# RC_car.net
KiCad netlist of a schematic drawn in EAGLE
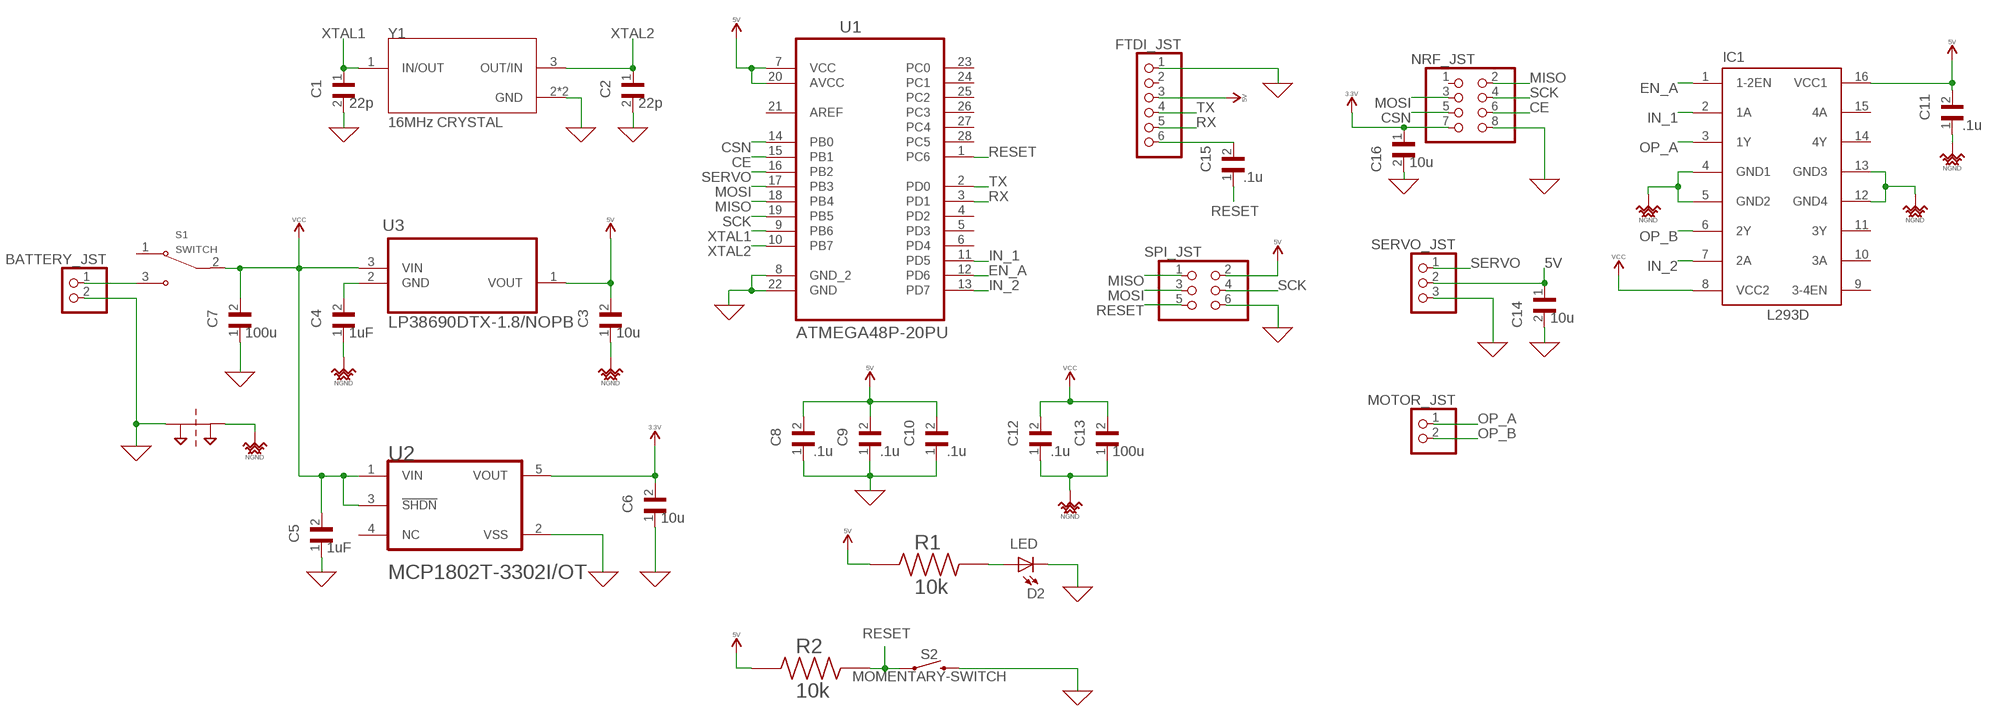
[diagram p0: schematic, sheet 1]

(export (version "E")
  (design (tool "Eeschema 10.0.6"))
  (components
    (comp (ref "BATTERY_JST")
      (value "PINHD-1X2")
      (footprint "eagle-import:1X02")
      (libsource (lib "eagle-import") (part "PINHD-1X2"))
    )
    (comp (ref "C1")
      (value "22p")
      (footprint "eagle-import:CAPC2012X140N")
      (fields
        (field (name "DIGI-KEY_PART_NUMBER") "399-C0805C220J5GAC7800CT-ND")
        (field (name "MF") "KEMET")
        (field (name "MP") "C0805C220J5GACTU")
      )
      (libsource (lib "eagle-import") (part "C0805C220J5GACTU"))
    )
    (comp (ref "C2")
      (value "22p")
      (footprint "eagle-import:CAPC2012X140N")
      (fields
        (field (name "DIGI-KEY_PART_NUMBER") "399-C0805C220J5GAC7800CT-ND")
        (field (name "MF") "KEMET")
        (field (name "MP") "C0805C220J5GACTU")
      )
      (libsource (lib "eagle-import") (part "C0805C220J5GACTU"))
    )
    (comp (ref "C3")
      (value "10u")
      (footprint "eagle-import:CAPC2013X95N")
      (fields
        (field (name "DIGI-KEY_PART_NUMBER") "587-2980-1-ND")
        (field (name "MF") "Taiyo Yuden")
        (field (name "MP") "EMK212ABJ106KD-T")
      )
      (libsource (lib "eagle-import") (part "EMK212ABJ106KD-T"))
    )
    (comp (ref "C4")
      (value "1uF")
      (footprint "eagle-import:CAPC2012X70N")
      (fields
        (field (name "DIGI-KEY_PART_NUMBER") "490-1700-1-ND")
        (field (name "MF") "Murata")
        (field (name "MP") "GRM216R61E105KA12D")
      )
      (libsource (lib "eagle-import") (part "GRM216R61E105KA12D"))
    )
    (comp (ref "C5")
      (value "1uF")
      (footprint "eagle-import:CAPC2012X70N")
      (fields
        (field (name "DIGI-KEY_PART_NUMBER") "490-1700-1-ND")
        (field (name "MF") "Murata")
        (field (name "MP") "GRM216R61E105KA12D")
      )
      (libsource (lib "eagle-import") (part "GRM216R61E105KA12D"))
    )
    (comp (ref "C6")
      (value "10u")
      (footprint "eagle-import:CAPC2013X95N")
      (fields
        (field (name "DIGI-KEY_PART_NUMBER") "587-2980-1-ND")
        (field (name "MF") "Taiyo Yuden")
        (field (name "MP") "EMK212ABJ106KD-T")
      )
      (libsource (lib "eagle-import") (part "EMK212ABJ106KD-T"))
    )
    (comp (ref "C7")
      (value "100u")
      (footprint "eagle-import:CAPC3225X280N")
      (fields
        (field (name "DIGI-KEY_PART_NUMBER") "587-4317-1-ND")
        (field (name "MF") "Taiyo Yuden")
        (field (name "MP") "LMK325ABJ107MM-P")
      )
      (libsource (lib "eagle-import") (part "LMK325ABJ107MM-P"))
    )
    (comp (ref "C8")
      (value ".1u")
      (footprint "eagle-import:CAPC2012X140N")
      (fields
        (field (name "DIGI-KEY_PART_NUMBER") "478-3614-1-ND")
        (field (name "MF") "AVX")
        (field (name "MP") "08055F104K4T2A")
      )
      (libsource (lib "eagle-import") (part "08055F104K4T2A"))
    )
    (comp (ref "C9")
      (value ".1u")
      (footprint "eagle-import:CAPC2012X140N")
      (fields
        (field (name "DIGI-KEY_PART_NUMBER") "478-3614-1-ND")
        (field (name "MF") "AVX")
        (field (name "MP") "08055F104K4T2A")
      )
      (libsource (lib "eagle-import") (part "08055F104K4T2A"))
    )
    (comp (ref "C10")
      (value ".1u")
      (footprint "eagle-import:CAPC2012X140N")
      (fields
        (field (name "DIGI-KEY_PART_NUMBER") "478-3614-1-ND")
        (field (name "MF") "AVX")
        (field (name "MP") "08055F104K4T2A")
      )
      (libsource (lib "eagle-import") (part "08055F104K4T2A"))
    )
    (comp (ref "C11")
      (value ".1u")
      (footprint "eagle-import:CAPC2012X140N")
      (fields
        (field (name "DIGI-KEY_PART_NUMBER") "478-3614-1-ND")
        (field (name "MF") "AVX")
        (field (name "MP") "08055F104K4T2A")
      )
      (libsource (lib "eagle-import") (part "08055F104K4T2A"))
    )
    (comp (ref "C12")
      (value ".1u")
      (footprint "eagle-import:CAPC2012X140N")
      (fields
        (field (name "DIGI-KEY_PART_NUMBER") "478-3614-1-ND")
        (field (name "MF") "AVX")
        (field (name "MP") "08055F104K4T2A")
      )
      (libsource (lib "eagle-import") (part "08055F104K4T2A"))
    )
    (comp (ref "C13")
      (value "100u")
      (footprint "eagle-import:CAPC3225X280N")
      (fields
        (field (name "DIGI-KEY_PART_NUMBER") "587-4317-1-ND")
        (field (name "MF") "Taiyo Yuden")
        (field (name "MP") "LMK325ABJ107MM-P")
      )
      (libsource (lib "eagle-import") (part "LMK325ABJ107MM-P"))
    )
    (comp (ref "C14")
      (value "10u")
      (footprint "eagle-import:CAPC1608X90")
      (fields
        (field (name "DIGI-KEY_PART_NUMBER") "478-9701-1-ND")
        (field (name "MF") "AVX")
        (field (name "MP") "F381A106MMAAH1")
      )
      (libsource (lib "eagle-import") (part "F381A106MMAAH1"))
    )
    (comp (ref "C15")
      (value ".1u")
      (footprint "eagle-import:CAPC2012X140N")
      (fields
        (field (name "DIGI-KEY_PART_NUMBER") "478-3614-1-ND")
        (field (name "MF") "AVX")
        (field (name "MP") "08055F104K4T2A")
      )
      (libsource (lib "eagle-import") (part "08055F104K4T2A"))
    )
    (comp (ref "C16")
      (value "10u")
      (footprint "eagle-import:CAPC1608X90")
      (fields
        (field (name "DIGI-KEY_PART_NUMBER") "478-9701-1-ND")
        (field (name "MF") "AVX")
        (field (name "MP") "F381A106MMAAH1")
      )
      (libsource (lib "eagle-import") (part "F381A106MMAAH1"))
    )
    (comp (ref "D2")
      (value "LED")
      (footprint "eagle-import:DIOC200X125X110")
      (fields (field (name "MF") "Lite-On Electronics") (field (name "MP") "LTST-C170TBKT"))
      (libsource (lib "eagle-import") (part "LTST-C170TBKT"))
    )
    (comp (ref "FTDI_JST")
      (value "PINHD-1X6")
      (footprint "eagle-import:1X06")
      (libsource (lib "eagle-import") (part "PINHD-1X6"))
    )
    (comp (ref "IC1")
      (value "L293D")
      (footprint "eagle-import:DIL16")
      (libsource (lib "eagle-import") (part "L293D"))
    )
    (comp (ref "MOTOR_JST")
      (value "PINHD-1X2")
      (footprint "eagle-import:1X02")
      (libsource (lib "eagle-import") (part "PINHD-1X2"))
    )
    (comp (ref "NET_BRIDGE1")
      (value "NET_BRIDGE")
      (footprint "eagle-import:NET_BRIDGE")
      (libsource (lib "eagle-import") (part "NET_BRIDGE"))
    )
    (comp (ref "NRF_JST")
      (value "PINHD-2X4")
      (footprint "eagle-import:2X04")
      (libsource (lib "eagle-import") (part "PINHD-2X4"))
    )
    (comp (ref "R1")
      (value "10k")
      (footprint "eagle-import:RESC2012X60N")
      (fields
        (field (name "DIGI-KEY_PART_NUMBER") "CR0805-FX-1002ELFCT-ND")
        (field (name "MF") "Bourns")
        (field (name "MP") "CR0805-FX-1002ELF")
      )
      (libsource (lib "eagle-import") (part "CR0805-FX-1002ELF"))
    )
    (comp (ref "R2")
      (value "10k")
      (footprint "eagle-import:RESC2012X60N")
      (fields
        (field (name "DIGI-KEY_PART_NUMBER") "CR0805-FX-1002ELFCT-ND")
        (field (name "MF") "Bourns")
        (field (name "MP") "CR0805-FX-1002ELF")
      )
      (libsource (lib "eagle-import") (part "CR0805-FX-1002ELF"))
    )
    (comp (ref "S1")
      (value "SWITCH")
      (footprint "eagle-import:SW_500SSP1S2M2QEA")
      (fields
        (field (name "DIGI-KEY_PART_NUMBER") "EG5137-ND")
        (field (name "MF") "E-Switch")
        (field (name "MP") "500SSP1S2M2QEA")
      )
      (libsource (lib "eagle-import") (part "500SSP1S2M2QEA"))
    )
    (comp (ref "S2")
      (value "MOMENTARY-SWITCH")
      (footprint "eagle-import:TACTILE_SWITCH_PTH_6.0MM")
      (libsource (lib "eagle-import") (part "MOMENTARY-SWITCH-SPST-PTH-6.0MM"))
    )
    (comp (ref "SERVO_JST")
      (value "PINHD-1X3")
      (footprint "eagle-import:1X03")
      (libsource (lib "eagle-import") (part "PINHD-1X3"))
    )
    (comp (ref "SPI_JST")
      (value "PINHD-2X3")
      (footprint "eagle-import:2X03")
      (libsource (lib "eagle-import") (part "PINHD-2X3"))
    )
    (comp (ref "U1")
      (value "ATMEGA48P-20PU")
      (footprint "eagle-import:DIP254P762X457-28")
      (fields (field (name "DIGI-KEY_PART_NUMBER") "ATMEGA48P-20PU-ND") (field (name "MF") "Microchip"))
      (libsource (lib "eagle-import") (part "ATMEGA48P-20PU"))
    )
    (comp (ref "U2")
      (value "MICROCHIP_MCP1802T-3302I-OTMICROCHIP_MCP1802T-3302I-OT_0_0")
      (footprint "eagle-import:MICROCHIP_MCP1802T-3302I-OT_0")
      (fields
        (field (name "DIGIKEY_PART_NUMBER") "MCP1802T-3302I/OTCT-ND")
        (field (name "MF") "Microchip")
        (field (name "MOUSER_PART_NUMBER") "579-MCP1802T-3302IOT")
      )
      (libsource (lib "eagle-import") (part "MICROCHIP_MCP1802T-3302I-OTMICROCHIP_MCP1802T-3302I-OT_0_0"))
    )
    (comp (ref "U3")
      (value "LP38690DTX-1.8/NOPB")
      (footprint "eagle-import:TO228P1042X238-3N")
      (fields (field (name "MF") "Texas Instruments"))
      (libsource (lib "eagle-import") (part "LP38690DTX-1.8/NOPB"))
    )
    (comp (ref "Y1")
      (value "16MHz CRYSTAL")
      (footprint "eagle-import:XTAL_ECS-160-12-33-AGN-TR")
      (fields
        (field (name "DIGI-KEY_PART_NUMBER") "XC2930CT-ND")
        (field (name "MF") "ECS Inc.")
        (field (name "MP") "ECS-160-12-33-AGN-TR")
      )
      (libsource (lib "eagle-import") (part "ECS-160-12-33-AGN-TR"))
    )
  )
  (nets
    (net (code "1") (name "/CE") (class "Default")
      (node (ref "NRF_JST") (pin "6") (pinfunction "6_6") (pintype "passive"))
      (node (ref "U1") (pin "15") (pinfunction "PB1_15") (pintype "bidirectional"))
    )
    (net (code "2") (name "/CSN") (class "Default")
      (node (ref "NRF_JST") (pin "5") (pinfunction "5_5") (pintype "passive"))
      (node (ref "U1") (pin "14") (pinfunction "PB0_14") (pintype "bidirectional"))
    )
    (net (code "3") (name "/EN_A") (class "Default")
      (node (ref "IC1") (pin "1") (pinfunction "1-2EN_1") (pintype "input"))
      (node (ref "U1") (pin "12") (pinfunction "PD6_12") (pintype "bidirectional"))
    )
    (net (code "4") (name "/IN_1") (class "Default")
      (node (ref "IC1") (pin "2") (pinfunction "1A_2") (pintype "input"))
      (node (ref "U1") (pin "11") (pinfunction "PD5_11") (pintype "bidirectional"))
    )
    (net (code "5") (name "/IN_2") (class "Default")
      (node (ref "IC1") (pin "7") (pinfunction "2A_7") (pintype "input"))
      (node (ref "U1") (pin "13") (pinfunction "PD7_13") (pintype "bidirectional"))
    )
    (net (code "6") (name "/MISO") (class "Default")
      (node (ref "NRF_JST") (pin "2") (pinfunction "2_2") (pintype "passive"))
      (node (ref "SPI_JST") (pin "1") (pinfunction "1_1") (pintype "passive"))
      (node (ref "U1") (pin "18") (pinfunction "PB4_18") (pintype "bidirectional"))
    )
    (net (code "7") (name "/MOSI") (class "Default")
      (node (ref "NRF_JST") (pin "3") (pinfunction "3_3") (pintype "passive"))
      (node (ref "SPI_JST") (pin "3") (pinfunction "3_3") (pintype "passive"))
      (node (ref "U1") (pin "17") (pinfunction "PB3_17") (pintype "bidirectional"))
    )
    (net (code "8") (name "/OP_A") (class "Default")
      (node (ref "IC1") (pin "3") (pinfunction "1Y_3") (pintype "output"))
      (node (ref "MOTOR_JST") (pin "1") (pinfunction "1_1") (pintype "passive"))
    )
    (net (code "9") (name "/OP_B") (class "Default")
      (node (ref "IC1") (pin "6") (pinfunction "2Y_6") (pintype "output"))
      (node (ref "MOTOR_JST") (pin "2") (pinfunction "2_2") (pintype "passive"))
    )
    (net (code "10") (name "/RESET") (class "Default")
      (node (ref "C15") (pin "1") (pinfunction "1_1") (pintype "passive"))
      (node (ref "R2") (pin "2") (pinfunction "2_2") (pintype "passive"))
      (node (ref "S2") (pin "1") (pinfunction "1_1") (pintype "passive"))
      (node (ref "SPI_JST") (pin "5") (pinfunction "5_5") (pintype "passive"))
      (node (ref "U1") (pin "1") (pinfunction "PC6_1") (pintype "bidirectional"))
    )
    (net (code "11") (name "/RX") (class "Default")
      (node (ref "FTDI_JST") (pin "5") (pinfunction "5_5") (pintype "passive"))
      (node (ref "U1") (pin "3") (pinfunction "PD1_3") (pintype "bidirectional"))
    )
    (net (code "12") (name "/SCK") (class "Default")
      (node (ref "NRF_JST") (pin "4") (pinfunction "4_4") (pintype "passive"))
      (node (ref "SPI_JST") (pin "4") (pinfunction "4_4") (pintype "passive"))
      (node (ref "U1") (pin "19") (pinfunction "PB5_19") (pintype "bidirectional"))
    )
    (net (code "13") (name "/SERVO") (class "Default")
      (node (ref "SERVO_JST") (pin "1") (pinfunction "1_1") (pintype "passive"))
      (node (ref "U1") (pin "16") (pinfunction "PB2_16") (pintype "bidirectional"))
    )
    (net (code "14") (name "/TX") (class "Default")
      (node (ref "FTDI_JST") (pin "4") (pinfunction "4_4") (pintype "passive"))
      (node (ref "U1") (pin "2") (pinfunction "PD0_2") (pintype "bidirectional"))
    )
    (net (code "15") (name "/XTAL1") (class "Default")
      (node (ref "C1") (pin "1") (pinfunction "1_1") (pintype "passive"))
      (node (ref "U1") (pin "9") (pinfunction "PB6_9") (pintype "bidirectional"))
      (node (ref "Y1") (pin "1") (pinfunction "IN/OUT_1") (pintype "bidirectional"))
    )
    (net (code "16") (name "/XTAL2") (class "Default")
      (node (ref "C2") (pin "1") (pinfunction "1_1") (pintype "passive"))
      (node (ref "U1") (pin "10") (pinfunction "PB7_10") (pintype "bidirectional"))
      (node (ref "Y1") (pin "3") (pinfunction "OUT/IN_3") (pintype "bidirectional"))
    )
    (net (code "17") (name "3.3V") (class "Default")
      (node (ref "C16") (pin "1") (pinfunction "1_1") (pintype "passive"))
      (node (ref "C6") (pin "2") (pinfunction "2_2") (pintype "passive"))
      (node (ref "NRF_JST") (pin "7") (pinfunction "7_7") (pintype "passive"))
      (node (ref "U2") (pin "5") (pinfunction "VOUT_5") (pintype "power_in"))
    )
    (net (code "18") (name "5V") (class "Default")
      (node (ref "C10") (pin "2") (pinfunction "2_2") (pintype "passive"))
      (node (ref "C11") (pin "2") (pinfunction "2_2") (pintype "passive"))
      (node (ref "C14") (pin "1") (pinfunction "1_1") (pintype "passive"))
      (node (ref "C3") (pin "2") (pinfunction "2_2") (pintype "passive"))
      (node (ref "C8") (pin "2") (pinfunction "2_2") (pintype "passive"))
      (node (ref "C9") (pin "2") (pinfunction "2_2") (pintype "passive"))
      (node (ref "FTDI_JST") (pin "3") (pinfunction "3_3") (pintype "passive"))
      (node (ref "IC1") (pin "16") (pinfunction "VCC1_16") (pintype "power_in"))
      (node (ref "R1") (pin "1") (pinfunction "1_1") (pintype "passive"))
      (node (ref "R2") (pin "1") (pinfunction "1_1") (pintype "passive"))
      (node (ref "SERVO_JST") (pin "2") (pinfunction "2_2") (pintype "passive"))
      (node (ref "SPI_JST") (pin "2") (pinfunction "2_2") (pintype "passive"))
      (node (ref "U1") (pin "20") (pinfunction "AVCC_20") (pintype "power_in"))
      (node (ref "U1") (pin "7") (pinfunction "VCC_7") (pintype "power_in"))
      (node (ref "U3") (pin "1") (pinfunction "VOUT_1") (pintype "output"))
    )
    (net (code "19") (name "GND") (class "Default")
      (node (ref "BATTERY_JST") (pin "2") (pinfunction "2_2") (pintype "passive"))
      (node (ref "C1") (pin "2") (pinfunction "2_2") (pintype "passive"))
      (node (ref "C10") (pin "1") (pinfunction "1_1") (pintype "passive"))
      (node (ref "C14") (pin "2") (pinfunction "2_2") (pintype "passive"))
      (node (ref "C16") (pin "2") (pinfunction "2_2") (pintype "passive"))
      (node (ref "C2") (pin "2") (pinfunction "2_2") (pintype "passive"))
      (node (ref "C5") (pin "1") (pinfunction "1_1") (pintype "passive"))
      (node (ref "C6") (pin "1") (pinfunction "1_1") (pintype "passive"))
      (node (ref "C7") (pin "1") (pinfunction "1_1") (pintype "passive"))
      (node (ref "C8") (pin "1") (pinfunction "1_1") (pintype "passive"))
      (node (ref "C9") (pin "1") (pinfunction "1_1") (pintype "passive"))
      (node (ref "D2") (pin "-") (pinfunction "-_-") (pintype "passive"))
      (node (ref "FTDI_JST") (pin "1") (pinfunction "1_1") (pintype "passive"))
      (node (ref "NET_BRIDGE1") (pin "P$1") (pinfunction "P$1_P$1") (pintype "passive"))
      (node (ref "NRF_JST") (pin "8") (pinfunction "8_8") (pintype "passive"))
      (node (ref "S2") (pin "3") (pinfunction "2_3") (pintype "passive"))
      (node (ref "SERVO_JST") (pin "3") (pinfunction "3_3") (pintype "passive"))
      (node (ref "SPI_JST") (pin "6") (pinfunction "6_6") (pintype "passive"))
      (node (ref "U1") (pin "22") (pinfunction "GND_22") (pintype "passive"))
      (node (ref "U1") (pin "8") (pinfunction "GND_2_8") (pintype "passive"))
      (node (ref "U2") (pin "2") (pinfunction "VSS_2") (pintype "power_in"))
      (node (ref "Y1") (pin "2") (pinfunction "GND_2") (pintype "power_in"))
      (node (ref "Y1") (pin "4") (pinfunction "GND_4") (pintype "power_in"))
    )
    (net (code "20") (name "NGND") (class "Default")
      (node (ref "C11") (pin "1") (pinfunction "1_1") (pintype "passive"))
      (node (ref "C12") (pin "1") (pinfunction "1_1") (pintype "passive"))
      (node (ref "C13") (pin "1") (pinfunction "1_1") (pintype "passive"))
      (node (ref "C3") (pin "1") (pinfunction "1_1") (pintype "passive"))
      (node (ref "C4") (pin "1") (pinfunction "1_1") (pintype "passive"))
      (node (ref "IC1") (pin "12") (pinfunction "GND4_12") (pintype "power_in"))
      (node (ref "IC1") (pin "13") (pinfunction "GND3_13") (pintype "power_in"))
      (node (ref "IC1") (pin "4") (pinfunction "GND1_4") (pintype "power_in"))
      (node (ref "IC1") (pin "5") (pinfunction "GND2_5") (pintype "power_in"))
      (node (ref "NET_BRIDGE1") (pin "P$2") (pinfunction "P$2_P$2") (pintype "passive"))
    )
    (net (code "21") (name "Net-(C15-Pad2)") (class "Default")
      (node (ref "C15") (pin "2") (pinfunction "2_2") (pintype "passive"))
      (node (ref "FTDI_JST") (pin "6") (pinfunction "6_6") (pintype "passive"))
    )
    (net (code "22") (name "Net-(D2-Pad+)") (class "Default")
      (node (ref "D2") (pin "+") (pinfunction "+_+") (pintype "passive"))
      (node (ref "R1") (pin "2") (pinfunction "2_2") (pintype "passive"))
    )
    (net (code "23") (name "Net-(S1-NO)") (class "Default")
      (node (ref "BATTERY_JST") (pin "1") (pinfunction "1_1") (pintype "passive"))
      (node (ref "S1") (pin "3") (pinfunction "NO_3") (pintype "passive"))
    )
    (net (code "24") (name "Net-(U3-GND)") (class "Default")
      (node (ref "C4") (pin "2") (pinfunction "2_2") (pintype "passive"))
      (node (ref "U3") (pin "2") (pinfunction "GND_2") (pintype "passive"))
    )
    (net (code "25") (name "VCC") (class "Default")
      (node (ref "C12") (pin "2") (pinfunction "2_2") (pintype "passive"))
      (node (ref "C13") (pin "2") (pinfunction "2_2") (pintype "passive"))
      (node (ref "C5") (pin "2") (pinfunction "2_2") (pintype "passive"))
      (node (ref "C7") (pin "2") (pinfunction "2_2") (pintype "passive"))
      (node (ref "IC1") (pin "8") (pinfunction "VCC2_8") (pintype "power_in"))
      (node (ref "S1") (pin "2") (pinfunction "COM_2") (pintype "passive"))
      (node (ref "U2") (pin "1") (pinfunction "VIN_1") (pintype "power_in"))
      (node (ref "U2") (pin "3") (pinfunction "~{SHDN}_3") (pintype "input"))
      (node (ref "U3") (pin "3") (pinfunction "VIN_3") (pintype "input"))
    )
    (net (code "26") (name "unconnected-(FTDI_JST-Pad2)") (class "Default")
      (node (ref "FTDI_JST") (pin "2") (pinfunction "2_2") (pintype "passive"))
    )
    (net (code "27") (name "unconnected-(IC1-3-4EN-Pad9)") (class "Default")
      (node (ref "IC1") (pin "9") (pinfunction "3-4EN_9") (pintype "input"))
    )
    (net (code "28") (name "unconnected-(IC1-3A-Pad10)") (class "Default")
      (node (ref "IC1") (pin "10") (pinfunction "3A_10") (pintype "input"))
    )
    (net (code "29") (name "unconnected-(IC1-3Y-Pad11)") (class "Default")
      (node (ref "IC1") (pin "11") (pinfunction "3Y_11") (pintype "output"))
    )
    (net (code "30") (name "unconnected-(IC1-4A-Pad15)") (class "Default")
      (node (ref "IC1") (pin "15") (pinfunction "4A_15") (pintype "input"))
    )
    (net (code "31") (name "unconnected-(IC1-4Y-Pad14)") (class "Default")
      (node (ref "IC1") (pin "14") (pinfunction "4Y_14") (pintype "output"))
    )
    (net (code "32") (name "unconnected-(NRF_JST-Pad1)") (class "Default")
      (node (ref "NRF_JST") (pin "1") (pinfunction "1_1") (pintype "passive"))
    )
    (net (code "33") (name "unconnected-(S1-NC-Pad1)") (class "Default")
      (node (ref "S1") (pin "1") (pinfunction "NC_1") (pintype "passive"))
    )
    (net (code "34") (name "unconnected-(U1-AREF-Pad21)") (class "Default")
      (node (ref "U1") (pin "21") (pinfunction "AREF_21") (pintype "input"))
    )
    (net (code "35") (name "unconnected-(U1-PC0-Pad23)") (class "Default")
      (node (ref "U1") (pin "23") (pinfunction "PC0_23") (pintype "bidirectional"))
    )
    (net (code "36") (name "unconnected-(U1-PC1-Pad24)") (class "Default")
      (node (ref "U1") (pin "24") (pinfunction "PC1_24") (pintype "bidirectional"))
    )
    (net (code "37") (name "unconnected-(U1-PC2-Pad25)") (class "Default")
      (node (ref "U1") (pin "25") (pinfunction "PC2_25") (pintype "bidirectional"))
    )
    (net (code "38") (name "unconnected-(U1-PC3-Pad26)") (class "Default")
      (node (ref "U1") (pin "26") (pinfunction "PC3_26") (pintype "bidirectional"))
    )
    (net (code "39") (name "unconnected-(U1-PC4-Pad27)") (class "Default")
      (node (ref "U1") (pin "27") (pinfunction "PC4_27") (pintype "bidirectional"))
    )
    (net (code "40") (name "unconnected-(U1-PC5-Pad28)") (class "Default")
      (node (ref "U1") (pin "28") (pinfunction "PC5_28") (pintype "bidirectional"))
    )
    (net (code "41") (name "unconnected-(U1-PD2-Pad4)") (class "Default")
      (node (ref "U1") (pin "4") (pinfunction "PD2_4") (pintype "bidirectional"))
    )
    (net (code "42") (name "unconnected-(U1-PD3-Pad5)") (class "Default")
      (node (ref "U1") (pin "5") (pinfunction "PD3_5") (pintype "bidirectional"))
    )
    (net (code "43") (name "unconnected-(U1-PD4-Pad6)") (class "Default")
      (node (ref "U1") (pin "6") (pinfunction "PD4_6") (pintype "bidirectional"))
    )
    (net (code "44") (name "unconnected-(U2-NC-Pad4)") (class "Default")
      (node (ref "U2") (pin "4") (pinfunction "NC_4") (pintype "passive"))
    )
  )
)
